# VariableStoboscope_Rev1_0.net
KiCad netlist of a schematic drawn in Altium Designer
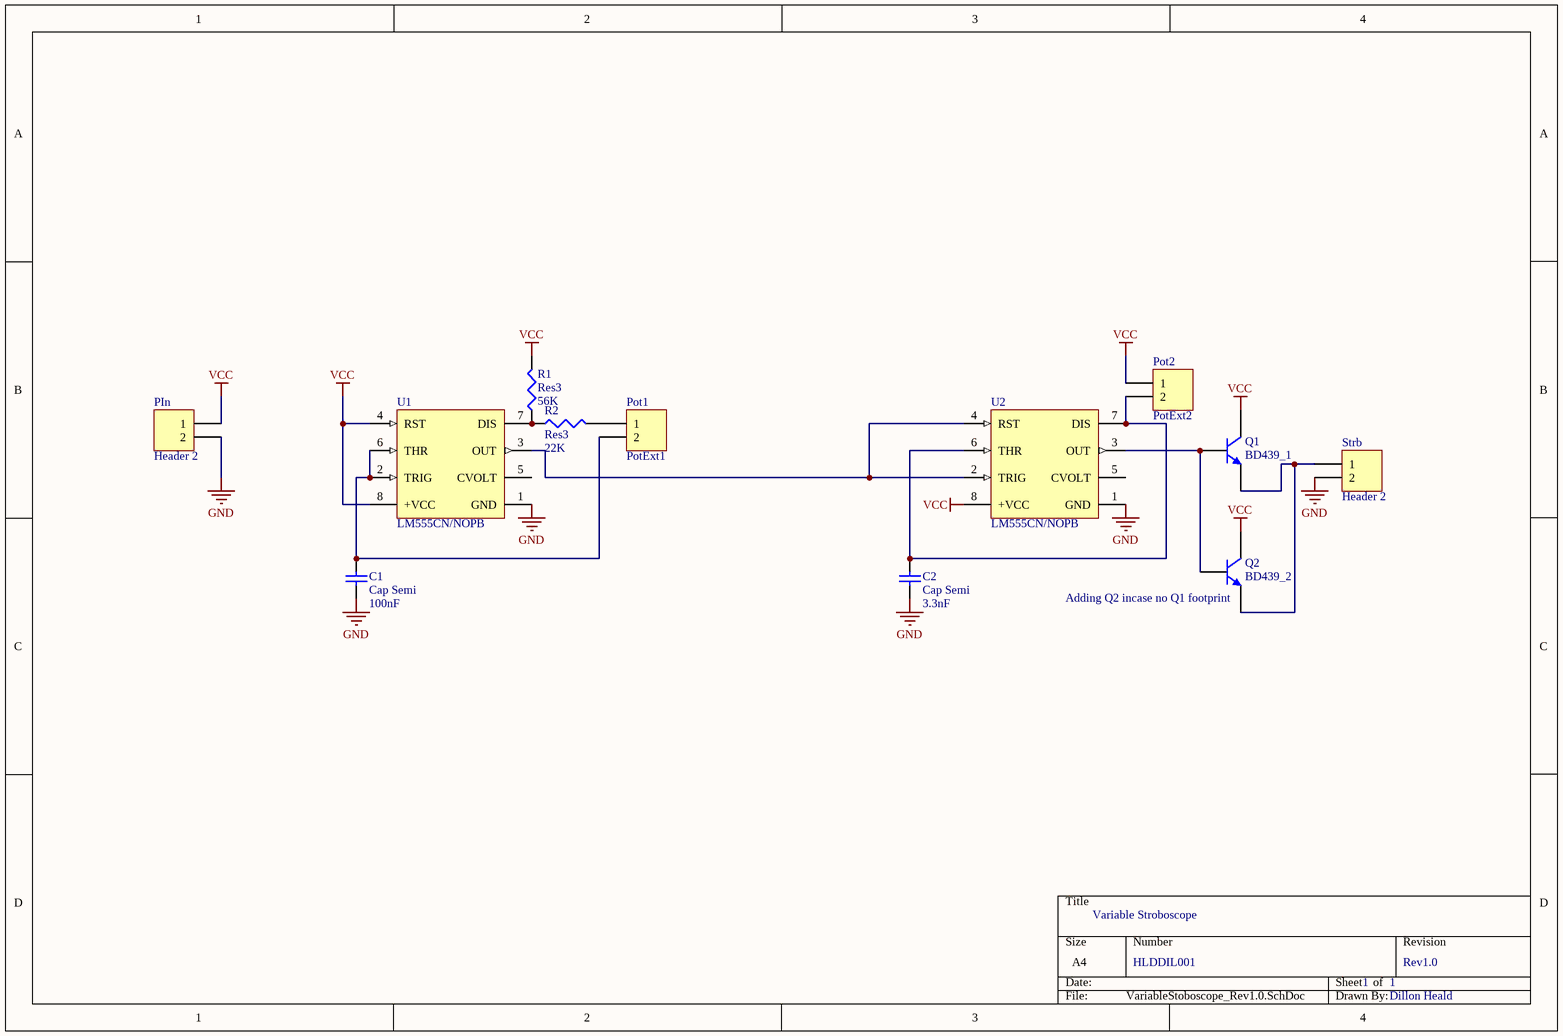
[diagram p0: VariableStoboscope_Rev1.0.SchDoc]

(export (version "E")
  (design (tool "Eeschema 10.0.6"))
  (components
    (comp (ref "C1")
      (value "Cap Semi")
      (footprint "C1206")
      (description "Capacitor (Semiconductor SIM Model)")
      (fields (field (name "ALTIUM_VALUE") "100nF") (field (name "PUBLISHER") "Altium Limited"))
      (libsource (lib "Miscellaneous Devices") (part "Cap Semi"))
    )
    (comp (ref "C2")
      (value "Cap Semi")
      (footprint "C1206")
      (description "Capacitor (Semiconductor SIM Model)")
      (fields (field (name "ALTIUM_VALUE") "3.3nF") (field (name "PUBLISHER") "Altium Limited"))
      (libsource (lib "Miscellaneous Devices") (part "Cap Semi"))
    )
    (comp (ref "PIn")
      (value "Header 2")
      (footprint "HDR1X2")
      (description "Header, 2-Pin")
      (fields (field (name "PUBLISHER") "Altium Limited"))
      (libsource (lib "") (part "Header 2_1"))
    )
    (comp (ref "Pot1")
      (value "PotExt1")
      (footprint "HDR1X2")
      (description "Header, 2-Pin")
      (fields (field (name "PUBLISHER") "Altium Limited"))
      (libsource (lib "Miscellaneous Connectors") (part "Header 2"))
    )
    (comp (ref "Pot2")
      (value "PotExt2")
      (footprint "HDR1X2")
      (description "Header, 2-Pin")
      (fields (field (name "PUBLISHER") "Altium Limited"))
      (libsource (lib "Miscellaneous Connectors") (part "Header 2"))
    )
    (comp (ref "Q1")
      (value "BD439_1")
      (footprint "SOT-23B_M")
      (description "NPN Bipolar Transistor")
      (fields (field (name "PUBLISHER") "Altium Limited"))
      (libsource (lib "Miscellaneous Devices") (part "QNPN"))
    )
    (comp (ref "Q2")
      (value "BD439_2")
      (footprint "TO-226-AA")
      (description "NPN Bipolar Transistor")
      (fields (field (name "PUBLISHER") "Altium Limited"))
      (libsource (lib "Miscellaneous Devices") (part "NPN"))
    )
    (comp (ref "R1")
      (value "Res3")
      (footprint "J1-0603")
      (description "Resistor")
      (fields (field (name "ALTIUM_VALUE") "56K") (field (name "PUBLISHER") "Altium Limited"))
      (libsource (lib "Miscellaneous Devices") (part "Res3"))
    )
    (comp (ref "R2")
      (value "Res3")
      (footprint "J1-0603")
      (description "Resistor")
      (fields (field (name "ALTIUM_VALUE") "22K") (field (name "PUBLISHER") "Altium Limited"))
      (libsource (lib "Miscellaneous Devices") (part "Res3"))
    )
    (comp (ref "Strb")
      (value "Header 2")
      (footprint "HDR1X2")
      (description "Header, 2-Pin")
      (fields (field (name "PUBLISHER") "Altium Limited"))
      (libsource (lib "Miscellaneous Connectors") (part "Header 2"))
    )
    (comp (ref "U1")
      (value "LM555CN/NOPB")
      (footprint "N08E")
      (description "Timer, 8-pin MDIP, Pb-Free")
      (fields (field (name "MANUFACTURER") "National Semiconductor"))
      (libsource (lib "Altium Content Vault") (part "AN-TIMER-LM555-8"))
    )
    (comp (ref "U2")
      (value "LM555CN/NOPB")
      (footprint "N08E")
      (description "Timer, 8-pin MDIP, Pb-Free")
      (fields (field (name "MANUFACTURER") "National Semiconductor"))
      (libsource (lib "Altium Content Vault") (part "AN-TIMER-LM555-8"))
    )
  )
  (nets
    (net (code "1") (name "GND") (class "Default")
      (node (ref "C1") (pin "1") (pinfunction "1_1") (pintype "passive"))
      (node (ref "C2") (pin "1") (pinfunction "1_1") (pintype "passive"))
      (node (ref "PIn") (pin "2") (pinfunction "2_2") (pintype "passive"))
      (node (ref "Strb") (pin "2") (pinfunction "2_2") (pintype "passive"))
      (node (ref "U1") (pin "1") (pinfunction "GND_1") (pintype "power_in"))
      (node (ref "U2") (pin "1") (pinfunction "GND_1") (pintype "power_in"))
    )
    (net (code "2") (name "Net-(Pot1-Pad1)") (class "Default")
      (node (ref "Pot1") (pin "1") (pinfunction "1_1") (pintype "passive"))
      (node (ref "R2") (pin "2") (pinfunction "2_2") (pintype "passive"))
    )
    (net (code "3") (name "Net-(Q1-B)") (class "Default")
      (node (ref "Q1") (pin "2") (pinfunction "B_2") (pintype "passive"))
      (node (ref "Q2") (pin "2") (pinfunction "B_2") (pintype "passive"))
      (node (ref "U2") (pin "3") (pinfunction "OUT_3") (pintype "output"))
    )
    (net (code "4") (name "Net-(Q1-E)") (class "Default")
      (node (ref "Q1") (pin "3") (pinfunction "E_3") (pintype "passive"))
      (node (ref "Q2") (pin "3") (pinfunction "E_3") (pintype "passive"))
      (node (ref "Strb") (pin "1") (pinfunction "1_1") (pintype "passive"))
    )
    (net (code "5") (name "Net-(U1-DIS)") (class "Default")
      (node (ref "R1") (pin "1") (pinfunction "1_1") (pintype "passive"))
      (node (ref "R2") (pin "1") (pinfunction "1_1") (pintype "passive"))
      (node (ref "U1") (pin "7") (pinfunction "DIS_7") (pintype "open_collector"))
    )
    (net (code "6") (name "Net-(U1-OUT)") (class "Default")
      (node (ref "U1") (pin "3") (pinfunction "OUT_3") (pintype "output"))
      (node (ref "U2") (pin "2") (pinfunction "TRIG_2") (pintype "input"))
      (node (ref "U2") (pin "4") (pinfunction "RST_4") (pintype "input"))
    )
    (net (code "7") (name "Net-(U1-THR)") (class "Default")
      (node (ref "C1") (pin "2") (pinfunction "2_2") (pintype "passive"))
      (node (ref "Pot1") (pin "2") (pinfunction "2_2") (pintype "passive"))
      (node (ref "U1") (pin "2") (pinfunction "TRIG_2") (pintype "input"))
      (node (ref "U1") (pin "6") (pinfunction "THR_6") (pintype "input"))
    )
    (net (code "8") (name "Net-(U2-DIS)") (class "Default")
      (node (ref "C2") (pin "2") (pinfunction "2_2") (pintype "passive"))
      (node (ref "Pot2") (pin "2") (pinfunction "2_2") (pintype "passive"))
      (node (ref "U2") (pin "6") (pinfunction "THR_6") (pintype "input"))
      (node (ref "U2") (pin "7") (pinfunction "DIS_7") (pintype "open_collector"))
    )
    (net (code "9") (name "VCC") (class "Default")
      (node (ref "PIn") (pin "1") (pinfunction "1_1") (pintype "passive"))
      (node (ref "Pot2") (pin "1") (pinfunction "1_1") (pintype "passive"))
      (node (ref "Q1") (pin "1") (pinfunction "C_1") (pintype "passive"))
      (node (ref "Q2") (pin "1") (pinfunction "C_1") (pintype "passive"))
      (node (ref "R1") (pin "2") (pinfunction "2_2") (pintype "passive"))
      (node (ref "U1") (pin "4") (pinfunction "RST_4") (pintype "input"))
      (node (ref "U1") (pin "8") (pinfunction "+VCC_8") (pintype "power_in"))
      (node (ref "U2") (pin "8") (pinfunction "+VCC_8") (pintype "power_in"))
    )
    (net (code "10") (name "unconnected-(U1-CVOLT-Pad5)") (class "Default")
      (node (ref "U1") (pin "5") (pinfunction "CVOLT_5") (pintype "passive"))
    )
    (net (code "11") (name "unconnected-(U2-CVOLT-Pad5)") (class "Default")
      (node (ref "U2") (pin "5") (pinfunction "CVOLT_5") (pintype "passive"))
    )
  )
)
